# breakout.net
KiCad netlist of a schematic drawn in Altium Designer
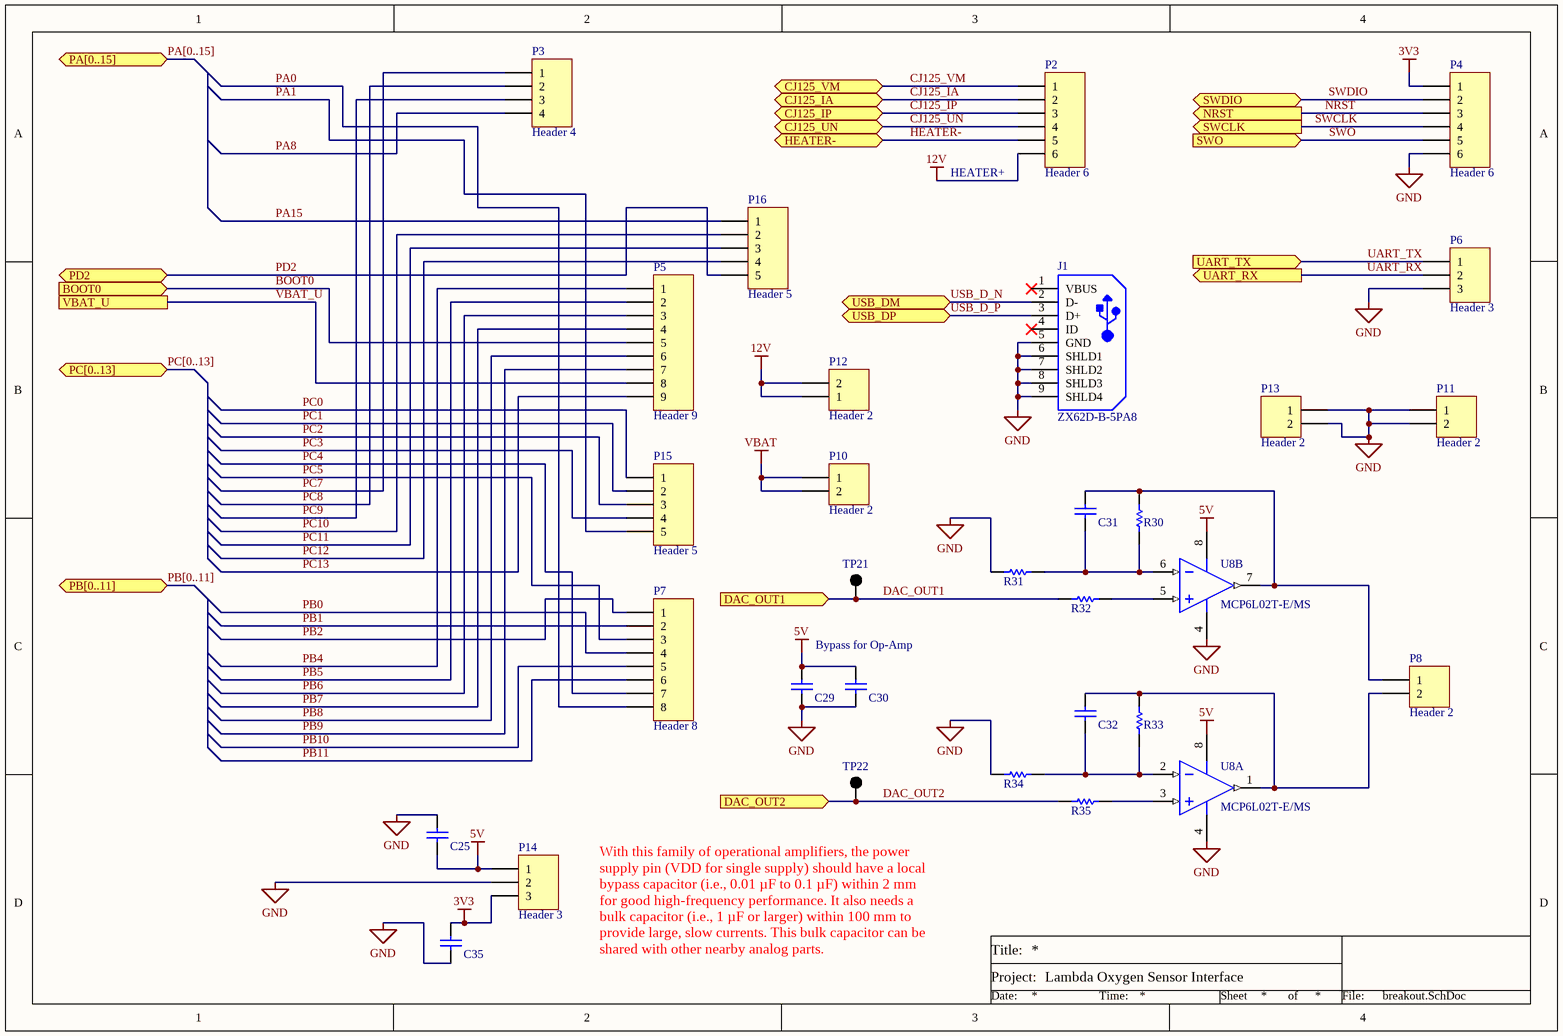
[diagram p0: breakout.SchDoc]

(export (version "E")
  (design (tool "Eeschema 10.0.6"))
  (components
    (comp (ref "C25")
      (value "Generic 0805 Capacitor")
      (footprint "0805")
      (libsource (lib "symbol_library") (part "C_0805"))
    )
    (comp (ref "C29")
      (value "Generic 0805 Capacitor")
      (footprint "0805")
      (libsource (lib "symbol_library") (part "C_0805"))
    )
    (comp (ref "C30")
      (value "Generic 0805 Capacitor")
      (footprint "0805")
      (libsource (lib "symbol_library") (part "C_0805"))
    )
    (comp (ref "C31")
      (value "Generic 0805 Capacitor")
      (footprint "0805")
      (libsource (lib "symbol_library") (part "C_0805"))
    )
    (comp (ref "C32")
      (value "Generic 0805 Capacitor")
      (footprint "0805")
      (libsource (lib "symbol_library") (part "C_0805"))
    )
    (comp (ref "C35")
      (value "Generic 0805 Capacitor")
      (footprint "0805")
      (libsource (lib "symbol_library") (part "C_0805"))
    )
    (comp (ref "J1")
      (value "ZX62D-B-5PA8")
      (footprint "HIRO-ZX62D-B-5PA8_V")
      (description "Micro-USB Connector Meeting USB 2.0 Standard, -30 to 85 degC, 5-Pin SMD, RoHS, Tape and Reel")
      (fields (field (name "MANUFACTURER") "HiroseElectric"))
      (libsource (lib "symbol_library") (part "Micro_USB"))
    )
    (comp (ref "P2")
      (value "Header 6")
      (footprint "HDR1X6")
      (description "Header, 6-Pin")
      (fields (field (name "PUBLISHER") "Altium Limited"))
      (libsource (lib "Miscellaneous Connectors") (part "Header 6"))
    )
    (comp (ref "P3")
      (value "Header 4")
      (footprint "HDR1X4")
      (description "Header, 4-Pin")
      (fields (field (name "PUBLISHER") "Altium Limited"))
      (libsource (lib "Miscellaneous Connectors") (part "Header 4"))
    )
    (comp (ref "P4")
      (value "Header 6")
      (footprint "HDR1X6")
      (description "Header, 6-Pin")
      (fields (field (name "PUBLISHER") "Altium Limited"))
      (libsource (lib "Miscellaneous Connectors") (part "Header 6"))
    )
    (comp (ref "P5")
      (value "Header 9")
      (footprint "HDR1X9")
      (description "Header, 9-Pin")
      (fields (field (name "PUBLISHER") "Altium Limited"))
      (libsource (lib "Miscellaneous Connectors") (part "Header 9"))
    )
    (comp (ref "P6")
      (value "Header 3")
      (footprint "HDR1X3")
      (description "Header, 3-Pin")
      (fields (field (name "PUBLISHER") "Altium Limited"))
      (libsource (lib "Miscellaneous Connectors") (part "Header 3"))
    )
    (comp (ref "P7")
      (value "Header 8")
      (footprint "HDR1X8")
      (description "Header, 8-Pin")
      (fields (field (name "PUBLISHER") "Altium Limited"))
      (libsource (lib "Miscellaneous Connectors") (part "Header 8"))
    )
    (comp (ref "P8")
      (value "Header 2")
      (footprint "HDR1X2")
      (description "Header, 2-Pin")
      (fields (field (name "PUBLISHER") "Altium Limited"))
      (libsource (lib "Miscellaneous Connectors") (part "Header 2"))
    )
    (comp (ref "P10")
      (value "Header 2")
      (footprint "HDR1X2")
      (description "Header, 2-Pin")
      (fields (field (name "PUBLISHER") "Altium Limited"))
      (libsource (lib "Miscellaneous Connectors") (part "Header 2"))
    )
    (comp (ref "P11")
      (value "Header 2")
      (footprint "HDR1X2")
      (description "Header, 2-Pin")
      (fields (field (name "PUBLISHER") "Altium Limited"))
      (libsource (lib "Miscellaneous Connectors") (part "Header 2"))
    )
    (comp (ref "P12")
      (value "Header 2")
      (footprint "HDR1X2")
      (description "Header, 2-Pin")
      (fields (field (name "PUBLISHER") "Altium Limited"))
      (libsource (lib "") (part "Header 2_1"))
    )
    (comp (ref "P13")
      (value "Header 2")
      (footprint "HDR1X2")
      (description "Header, 2-Pin")
      (fields (field (name "PUBLISHER") "Altium Limited"))
      (libsource (lib "") (part "Header 2_2"))
    )
    (comp (ref "P14")
      (value "Header 3")
      (footprint "HDR1X3")
      (description "Header, 3-Pin")
      (fields (field (name "PUBLISHER") "Altium Limited"))
      (libsource (lib "Miscellaneous Connectors") (part "Header 3"))
    )
    (comp (ref "P15")
      (value "Header 5")
      (footprint "HDR1X5")
      (description "Header, 5-Pin")
      (fields (field (name "PUBLISHER") "Altium Limited"))
      (libsource (lib "Miscellaneous Connectors") (part "Header 5"))
    )
    (comp (ref "P16")
      (value "Header 5")
      (footprint "HDR1X5")
      (description "Header, 5-Pin")
      (fields (field (name "PUBLISHER") "Altium Limited"))
      (libsource (lib "Miscellaneous Connectors") (part "Header 5"))
    )
    (comp (ref "R30")
      (value "Generic 0603 Resistor")
      (footprint "0603")
      (libsource (lib "symbol_library") (part "R_0603"))
    )
    (comp (ref "R31")
      (value "Generic 0603 Resistor")
      (footprint "0603")
      (libsource (lib "symbol_library") (part "R_0603"))
    )
    (comp (ref "R32")
      (value "Generic 0603 Resistor")
      (footprint "0603")
      (libsource (lib "symbol_library") (part "R_0603"))
    )
    (comp (ref "R33")
      (value "Generic 0603 Resistor")
      (footprint "0603")
      (libsource (lib "symbol_library") (part "R_0603"))
    )
    (comp (ref "R34")
      (value "Generic 0603 Resistor")
      (footprint "0603")
      (libsource (lib "symbol_library") (part "R_0603"))
    )
    (comp (ref "R35")
      (value "Generic 0603 Resistor")
      (footprint "0603")
      (libsource (lib "symbol_library") (part "R_0603"))
    )
    (comp (ref "TP21")
      (value "5001")
      (footprint "KSTN-5001")
      (description "Test Point, Black, 1-Pin THD, RoHS, Bulk")
      (fields (field (name "MANUFACTURER") "Keystone"))
      (libsource (lib "symbol_library") (part "TP5001"))
    )
    (comp (ref "TP22")
      (value "5001")
      (footprint "KSTN-5001")
      (description "Test Point, Black, 1-Pin THD, RoHS, Bulk")
      (fields (field (name "MANUFACTURER") "Keystone"))
      (libsource (lib "symbol_library") (part "TP5001"))
    )
    (comp (ref "U8")
      (value "MCP6L02T-E/MS")
      (footprint "MSOP8_M")
      (description "1 MHz, 85 渭A Dual Op Amp, 8-Pin MSOP, Extended Temperature Range, Tape and Reel")
      (libsource (lib "symbol_library") (part "MCP6L02"))
    )
  )
  (nets
    (net (code "15") (name "/BOOT0") (class "Default")
      (node (ref "P5") (pin "5") (pinfunction "5_5") (pintype "passive"))
    )
    (net (code "16") (name "/CJ125_IA") (class "Default")
      (node (ref "P2") (pin "2") (pinfunction "2_2") (pintype "passive"))
    )
    (net (code "17") (name "/CJ125_IP") (class "Default")
      (node (ref "P2") (pin "3") (pinfunction "3_3") (pintype "passive"))
    )
    (net (code "18") (name "/CJ125_UN") (class "Default")
      (node (ref "P2") (pin "4") (pinfunction "4_4") (pintype "passive"))
    )
    (net (code "19") (name "/CJ125_VM") (class "Default")
      (node (ref "P2") (pin "1") (pinfunction "1_1") (pintype "passive"))
    )
    (net (code "20") (name "/DAC_OUT1") (class "Default")
      (node (ref "R32") (pin "1") (pinfunction "1_1") (pintype "passive"))
      (node (ref "TP21") (pin "1") (pintype "passive"))
    )
    (net (code "21") (name "/DAC_OUT2") (class "Default")
      (node (ref "R35") (pin "1") (pinfunction "1_1") (pintype "passive"))
      (node (ref "TP22") (pin "1") (pintype "passive"))
    )
    (net (code "22") (name "/HEATER-") (class "Default")
      (node (ref "P2") (pin "5") (pinfunction "5_5") (pintype "passive"))
    )
    (net (code "23") (name "/NRST") (class "Default")
      (node (ref "P4") (pin "3") (pinfunction "3_3") (pintype "passive"))
    )
    (net (code "24") (name "/PA0") (class "Default")
      (node (ref "P7") (pin "8") (pinfunction "8_8") (pintype "passive"))
    )
    (net (code "25") (name "/PA1") (class "Default")
      (node (ref "P15") (pin "5") (pinfunction "5_5") (pintype "passive"))
    )
    (net (code "26") (name "/PA8") (class "Default")
      (node (ref "P3") (pin "4") (pinfunction "4_4") (pintype "passive"))
    )
    (net (code "27") (name "/PA15") (class "Default")
      (node (ref "P16") (pin "1") (pinfunction "1_1") (pintype "passive"))
    )
    (net (code "29") (name "/PB0") (class "Default")
      (node (ref "P7") (pin "4") (pinfunction "4_4") (pintype "passive"))
    )
    (net (code "30") (name "/PB1") (class "Default")
      (node (ref "P7") (pin "2") (pinfunction "2_2") (pintype "passive"))
    )
    (net (code "31") (name "/PB2") (class "Default")
      (node (ref "P7") (pin "1") (pinfunction "1_1") (pintype "passive"))
    )
    (net (code "32") (name "/PB4") (class "Default")
      (node (ref "P5") (pin "1") (pinfunction "1_1") (pintype "passive"))
    )
    (net (code "33") (name "/PB5") (class "Default")
      (node (ref "P5") (pin "2") (pinfunction "2_2") (pintype "passive"))
    )
    (net (code "34") (name "/PB6") (class "Default")
      (node (ref "P5") (pin "3") (pinfunction "3_3") (pintype "passive"))
    )
    (net (code "35") (name "/PB7") (class "Default")
      (node (ref "P5") (pin "4") (pinfunction "4_4") (pintype "passive"))
    )
    (net (code "36") (name "/PB8") (class "Default")
      (node (ref "P5") (pin "6") (pinfunction "6_6") (pintype "passive"))
    )
    (net (code "37") (name "/PB9") (class "Default")
      (node (ref "P5") (pin "7") (pinfunction "7_7") (pintype "passive"))
    )
    (net (code "38") (name "/PB10") (class "Default")
      (node (ref "P7") (pin "5") (pinfunction "5_5") (pintype "passive"))
    )
    (net (code "39") (name "/PB11") (class "Default")
      (node (ref "P7") (pin "6") (pinfunction "6_6") (pintype "passive"))
    )
    (net (code "41") (name "/PC0") (class "Default")
      (node (ref "P15") (pin "1") (pinfunction "1_1") (pintype "passive"))
    )
    (net (code "42") (name "/PC1") (class "Default")
      (node (ref "P15") (pin "2") (pinfunction "2_2") (pintype "passive"))
    )
    (net (code "43") (name "/PC2") (class "Default")
      (node (ref "P15") (pin "3") (pinfunction "3_3") (pintype "passive"))
    )
    (net (code "44") (name "/PC3") (class "Default")
      (node (ref "P15") (pin "4") (pinfunction "4_4") (pintype "passive"))
    )
    (net (code "45") (name "/PC4") (class "Default")
      (node (ref "P7") (pin "7") (pinfunction "7_7") (pintype "passive"))
    )
    (net (code "46") (name "/PC5") (class "Default")
      (node (ref "P7") (pin "3") (pinfunction "3_3") (pintype "passive"))
    )
    (net (code "47") (name "/PC7") (class "Default")
      (node (ref "P3") (pin "1") (pinfunction "1_1") (pintype "passive"))
    )
    (net (code "48") (name "/PC8") (class "Default")
      (node (ref "P3") (pin "2") (pinfunction "2_2") (pintype "passive"))
    )
    (net (code "49") (name "/PC9") (class "Default")
      (node (ref "P3") (pin "3") (pinfunction "3_3") (pintype "passive"))
    )
    (net (code "50") (name "/PC10") (class "Default")
      (node (ref "P16") (pin "2") (pinfunction "2_2") (pintype "passive"))
    )
    (net (code "51") (name "/PC11") (class "Default")
      (node (ref "P16") (pin "3") (pinfunction "3_3") (pintype "passive"))
    )
    (net (code "52") (name "/PC12") (class "Default")
      (node (ref "P16") (pin "4") (pinfunction "4_4") (pintype "passive"))
    )
    (net (code "53") (name "/PC13") (class "Default")
      (node (ref "P5") (pin "9") (pinfunction "9_9") (pintype "passive"))
    )
    (net (code "55") (name "/PD2") (class "Default")
      (node (ref "P16") (pin "5") (pinfunction "5_5") (pintype "passive"))
    )
    (net (code "56") (name "/SWCLK") (class "Default")
      (node (ref "P4") (pin "4") (pinfunction "4_4") (pintype "passive"))
    )
    (net (code "57") (name "/SWDIO") (class "Default")
      (node (ref "P4") (pin "2") (pinfunction "2_2") (pintype "passive"))
    )
    (net (code "58") (name "/SWO") (class "Default")
      (node (ref "P4") (pin "5") (pinfunction "5_5") (pintype "passive"))
    )
    (net (code "59") (name "/UART_RX") (class "Default")
      (node (ref "P6") (pin "2") (pinfunction "2_2") (pintype "passive"))
    )
    (net (code "60") (name "/UART_TX") (class "Default")
      (node (ref "P6") (pin "1") (pinfunction "1_1") (pintype "passive"))
    )
    (net (code "61") (name "/USB_D_N") (class "Default")
      (node (ref "J1") (pin "2") (pinfunction "D-_2") (pintype "passive"))
    )
    (net (code "62") (name "/USB_D_P") (class "Default")
      (node (ref "J1") (pin "3") (pinfunction "D+_3") (pintype "passive"))
    )
    (net (code "63") (name "/VBAT_U") (class "Default")
      (node (ref "P5") (pin "8") (pinfunction "8_8") (pintype "passive"))
    )
    (net (code "64") (name "3V3") (class "Default")
      (node (ref "C35") (pin "2") (pinfunction "2_2") (pintype "passive"))
      (node (ref "P14") (pin "3") (pinfunction "3_3") (pintype "passive"))
      (node (ref "P4") (pin "1") (pinfunction "1_1") (pintype "passive"))
    )
    (net (code "65") (name "5V") (class "Default")
      (node (ref "C25") (pin "2") (pinfunction "2_2") (pintype "passive"))
      (node (ref "C29") (pin "2") (pinfunction "2_2") (pintype "passive"))
      (node (ref "C30") (pin "2") (pinfunction "2_2") (pintype "passive"))
      (node (ref "P14") (pin "1") (pinfunction "1_1") (pintype "passive"))
      (node (ref "U8") (pin "8") (pinfunction "VDD_8") (pintype "power_in"))
    )
    (net (code "66") (name "12V") (class "Default")
      (node (ref "P12") (pin "1") (pinfunction "1_1") (pintype "passive"))
      (node (ref "P12") (pin "2") (pinfunction "2_2") (pintype "passive"))
      (node (ref "P2") (pin "6") (pinfunction "6_6") (pintype "passive"))
    )
    (net (code "67") (name "GND") (class "Default")
      (node (ref "C25") (pin "1") (pinfunction "1_1") (pintype "passive"))
      (node (ref "C29") (pin "1") (pinfunction "1_1") (pintype "passive"))
      (node (ref "C30") (pin "1") (pinfunction "1_1") (pintype "passive"))
      (node (ref "C35") (pin "1") (pinfunction "1_1") (pintype "passive"))
      (node (ref "J1") (pin "5") (pinfunction "GND_5") (pintype "passive"))
      (node (ref "J1") (pin "6") (pinfunction "SHLD1_6") (pintype "passive"))
      (node (ref "J1") (pin "7") (pinfunction "SHLD2_7") (pintype "passive"))
      (node (ref "J1") (pin "8") (pinfunction "SHLD3_8") (pintype "passive"))
      (node (ref "J1") (pin "9") (pinfunction "SHLD4_9") (pintype "passive"))
      (node (ref "P11") (pin "1") (pinfunction "1_1") (pintype "passive"))
      (node (ref "P11") (pin "2") (pinfunction "2_2") (pintype "passive"))
      (node (ref "P13") (pin "1") (pinfunction "1_1") (pintype "passive"))
      (node (ref "P13") (pin "2") (pinfunction "2_2") (pintype "passive"))
      (node (ref "P14") (pin "2") (pinfunction "2_2") (pintype "passive"))
      (node (ref "P4") (pin "6") (pinfunction "6_6") (pintype "passive"))
      (node (ref "P6") (pin "3") (pinfunction "3_3") (pintype "passive"))
      (node (ref "R31") (pin "1") (pinfunction "1_1") (pintype "passive"))
      (node (ref "R34") (pin "1") (pinfunction "1_1") (pintype "passive"))
      (node (ref "U8") (pin "4") (pinfunction "VSS_4") (pintype "power_in"))
    )
    (net (code "68") (name "Net-(U8A-VINA+)") (class "Default")
      (node (ref "R35") (pin "2") (pinfunction "2_2") (pintype "passive"))
      (node (ref "U8") (pin "3") (pinfunction "VINA+_3") (pintype "input"))
    )
    (net (code "69") (name "Net-(U8A-VINA-)") (class "Default")
      (node (ref "C32") (pin "1") (pinfunction "1_1") (pintype "passive"))
      (node (ref "R33") (pin "1") (pinfunction "1_1") (pintype "passive"))
      (node (ref "R34") (pin "2") (pinfunction "2_2") (pintype "passive"))
      (node (ref "U8") (pin "2") (pinfunction "VINA-_2") (pintype "input"))
    )
    (net (code "70") (name "Net-(U8A-VOUTA)") (class "Default")
      (node (ref "C32") (pin "2") (pinfunction "2_2") (pintype "passive"))
      (node (ref "P8") (pin "2") (pinfunction "2_2") (pintype "passive"))
      (node (ref "R33") (pin "2") (pinfunction "2_2") (pintype "passive"))
      (node (ref "U8") (pin "1") (pinfunction "VOUTA_1") (pintype "output"))
    )
    (net (code "71") (name "Net-(U8B-VINB+)") (class "Default")
      (node (ref "R32") (pin "2") (pinfunction "2_2") (pintype "passive"))
      (node (ref "U8") (pin "5") (pinfunction "VINB+_5") (pintype "input"))
    )
    (net (code "72") (name "Net-(U8B-VINB-)") (class "Default")
      (node (ref "C31") (pin "1") (pinfunction "1_1") (pintype "passive"))
      (node (ref "R30") (pin "1") (pinfunction "1_1") (pintype "passive"))
      (node (ref "R31") (pin "2") (pinfunction "2_2") (pintype "passive"))
      (node (ref "U8") (pin "6") (pinfunction "VINB-_6") (pintype "input"))
    )
    (net (code "73") (name "Net-(U8B-VOUTB)") (class "Default")
      (node (ref "C31") (pin "2") (pinfunction "2_2") (pintype "passive"))
      (node (ref "P8") (pin "1") (pinfunction "1_1") (pintype "passive"))
      (node (ref "R30") (pin "2") (pinfunction "2_2") (pintype "passive"))
      (node (ref "U8") (pin "7") (pinfunction "VOUTB_7") (pintype "output"))
    )
    (net (code "74") (name "VBAT") (class "Default")
      (node (ref "P10") (pin "1") (pinfunction "1_1") (pintype "passive"))
      (node (ref "P10") (pin "2") (pinfunction "2_2") (pintype "passive"))
    )
    (net (code "75") (name "unconnected-(J1-ID-Pad4)") (class "Default")
      (node (ref "J1") (pin "4") (pinfunction "ID_4") (pintype "passive+no_connect"))
    )
    (net (code "76") (name "unconnected-(J1-VBUS-Pad1)") (class "Default")
      (node (ref "J1") (pin "1") (pinfunction "VBUS_1") (pintype "passive+no_connect"))
    )
  )
)
